# 4_USB.net
KiCad netlist of a schematic drawn in Altium Designer
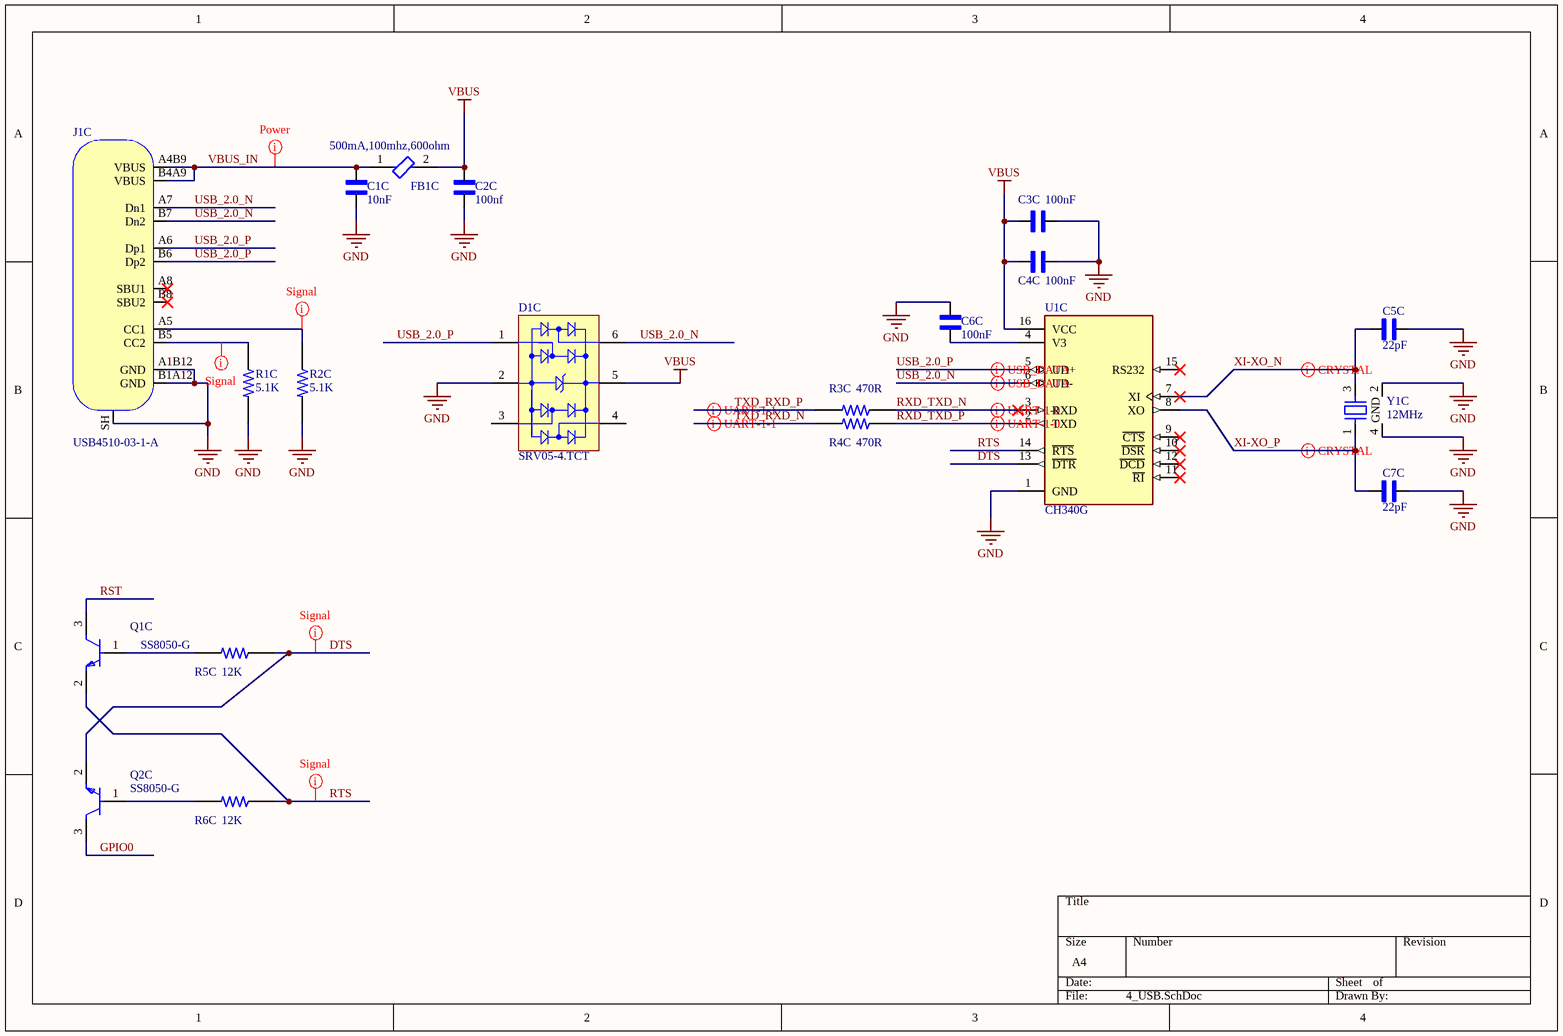
[diagram p0: 4_USB.SchDoc]

(export (version "E")
  (design (tool "Eeschema 10.0.6"))
  (components
    (comp (ref "C1C")
      (value "10nF")
      (footprint "C-0603")
      (description "Ceramic Capacitor 16V 0603 (1608 Metric)")
      (fields (field (name "MP") "C0603C104J4RAC") (field (name "MF") "KEMET"))
      (libsource (lib "ESP01-S-UART") (part "C-0603"))
    )
    (comp (ref "C2C")
      (value "100nf")
      (footprint "C-0603")
      (description "Ceramic Capacitor 16V 0603 (1608 Metric)")
      (fields (field (name "MP") "C0603C104J4RAC") (field (name "MF") "KEMET"))
      (libsource (lib "ESP01-S-UART") (part "C-0603"))
    )
    (comp (ref "C3C")
      (value "100nF")
      (footprint "C-0603")
      (description "Ceramic Capacitor 16V 0603 (1608 Metric)")
      (fields (field (name "MP") "C0603C104J4RAC") (field (name "MF") "KEMET"))
      (libsource (lib "") (part "C-0603_2"))
    )
    (comp (ref "C4C")
      (value "100nF")
      (footprint "C-0603")
      (description "Ceramic Capacitor 16V 0603 (1608 Metric)")
      (fields (field (name "MP") "C0603C104J4RAC") (field (name "MF") "KEMET"))
      (libsource (lib "") (part "C-0603_2"))
    )
    (comp (ref "C5C")
      (value "22pF")
      (footprint "C-0603")
      (description "Ceramic Capacitor 16V 0603 (1608 Metric)")
      (fields (field (name "MP") "C0603C104J4RAC") (field (name "MF") "KEMET"))
      (libsource (lib "") (part "C-0603_1"))
    )
    (comp (ref "C6C")
      (value "100nF")
      (footprint "C-0603")
      (description "Ceramic Capacitor 16V 0603 (1608 Metric)")
      (fields (field (name "MP") "C0603C104J4RAC") (field (name "MF") "KEMET"))
      (libsource (lib "") (part "C-0603_3"))
    )
    (comp (ref "C7C")
      (value "22pF")
      (footprint "C-0603")
      (description "Ceramic Capacitor 16V 0603 (1608 Metric)")
      (fields (field (name "MP") "C0603C104J4RAC") (field (name "MF") "KEMET"))
      (libsource (lib "") (part "C-0603_1"))
    )
    (comp (ref "D1C")
      (value "SRV05-4.TCT")
      (footprint "SMTC-SOT23-6_V")
      (fields (field (name "MANUFACTURER") "Semtech"))
      (libsource (lib "ESP01-S-UART") (part "STM-USB_DVI_HDMIULC6-4SC6X-SOT23-6L"))
    )
    (comp (ref "FB1C")
      (value "500mA,100mhz,600ohm")
      (footprint "FP-BLM21-0_2-t0_85-e0_5-IPC_A")
      (description "BLM21BB121SN1D")
      (fields (field (name "TOLERANCE") "25%"))
      (libsource (lib "ESP01-S-UART") (part "5f30dd21d616792df468990f7003faa"))
    )
    (comp (ref "J1C")
      (value "USB4510-03-1-A")
      (footprint "USB4510-03-1-A")
      (description "USB Connector Type C SMT Mid-Mount 16 Pin")
      (fields (field (name "MANUFACTURER") "GCT"))
      (libsource (lib "ESP01-S-UART") (part "USB4510-03-1-A"))
    )
    (comp (ref "Q1C")
      (value "SS8050-G")
      (footprint "FP-SS8050-G-MFG")
      (description "NPN TRANSISTOR 1.5A 40V SOT-23 R")
      (libsource (lib "ESP01-S-UART") (part "2a1388f82443b098dcd57d24ac7632d"))
    )
    (comp (ref "Q2C")
      (value "SS8050-G")
      (footprint "FP-SS8050-G-MFG")
      (description "NPN TRANSISTOR 1.5A 40V SOT-23 R")
      (libsource (lib "ESP01-S-UART") (part "2a1388f82443b098dcd57d24ac7632d"))
    )
    (comp (ref "R1C")
      (value "5.1K")
      (footprint "R-0603")
      (description "0603")
      (fields (field (name "MP") "2-1623703-0") (field (name "TOLERANCE") "1%"))
      (libsource (lib "ESP01-S-UART") (part "R-0603"))
    )
    (comp (ref "R2C")
      (value "5.1K")
      (footprint "R-0603")
      (description "0603")
      (fields (field (name "MP") "2-1623703-0") (field (name "TOLERANCE") "1%"))
      (libsource (lib "ESP01-S-UART") (part "R-0603"))
    )
    (comp (ref "R3C")
      (value "470R")
      (footprint "R-0603")
      (description "0603")
      (fields (field (name "MP") "2-1623703-0") (field (name "TOLERANCE") "1%"))
      (libsource (lib "ESP01-S-UART") (part "R-0603"))
    )
    (comp (ref "R4C")
      (value "470R")
      (footprint "R-0603")
      (description "0603")
      (fields (field (name "MP") "2-1623703-0") (field (name "TOLERANCE") "1%"))
      (libsource (lib "ESP01-S-UART") (part "R-0603"))
    )
    (comp (ref "R5C")
      (value "12K")
      (footprint "R-0603")
      (description "0603")
      (fields (field (name "MP") "2-1623703-0") (field (name "TOLERANCE") "1%"))
      (libsource (lib "ESP01-S-UART") (part "R-0603"))
    )
    (comp (ref "R6C")
      (value "12K")
      (footprint "R-0603")
      (description "0603")
      (fields (field (name "MP") "2-1623703-0") (field (name "TOLERANCE") "1%"))
      (libsource (lib "ESP01-S-UART") (part "R-0603"))
    )
    (comp (ref "U1C")
      (value "CH340G")
      (footprint "SOIC127P600X180-16N")
      (libsource (lib "ESP01-S-UART") (part "CH340G"))
    )
    (comp (ref "Y1C")
      (value "12MHz")
      (footprint "ABRACON ABM10")
      (description "CRYSTAL 12.00MHZ 8PF LOW ESR SMD")
      (fields
        (field (name "PART NUMBER") "ABM10-167-12.000MHZ-T3")
        (field (name "MANUFACTURER") "Abracon LLC")
      )
      (libsource (lib "ESP01-S-UART") (part "Abracon Crystal ABM10"))
    )
  )
  (nets
    (net (code "1") (name "/DTS") (class "Default")
      (node (ref "Q2C") (pin "2") (pinfunction "E_2") (pintype "passive"))
      (node (ref "R5C") (pin "1") (pinfunction "1_1") (pintype "passive"))
      (node (ref "U1C") (pin "13") (pinfunction "~{DTR}_13") (pintype "output"))
    )
    (net (code "2") (name "/GPIO0") (class "Default")
      (node (ref "Q2C") (pin "3") (pinfunction "C_3") (pintype "passive"))
    )
    (net (code "3") (name "/RST") (class "Default")
      (node (ref "Q1C") (pin "3") (pinfunction "C_3") (pintype "passive"))
    )
    (net (code "4") (name "/RTS") (class "Default")
      (node (ref "Q1C") (pin "2") (pinfunction "E_2") (pintype "passive"))
      (node (ref "R6C") (pin "1") (pinfunction "1_1") (pintype "passive"))
      (node (ref "U1C") (pin "14") (pinfunction "~{RTS}_14") (pintype "output"))
    )
    (net (code "5") (name "/RXD_TXD_N") (class "Default")
      (node (ref "R3C") (pin "1") (pinfunction "1_1") (pintype "passive"))
      (node (ref "U1C") (pin "3") (pinfunction "RXD_3") (pintype "input"))
    )
    (net (code "6") (name "/RXD_TXD_P") (class "Default")
      (node (ref "R4C") (pin "1") (pinfunction "1_1") (pintype "passive"))
      (node (ref "U1C") (pin "2") (pinfunction "TXD_2") (pintype "output"))
    )
    (net (code "7") (name "/TXD_RXD_N") (class "Default")
      (node (ref "R4C") (pin "2") (pinfunction "2_2") (pintype "passive"))
    )
    (net (code "8") (name "/TXD_RXD_P") (class "Default")
      (node (ref "R3C") (pin "2") (pinfunction "2_2") (pintype "passive"))
    )
    (net (code "9") (name "/USB_2.0_N") (class "Default")
      (node (ref "D1C") (pin "6") (pinfunction "I/O_4_6") (pintype "passive"))
      (node (ref "J1C") (pin "A7") (pinfunction "Dn1_A7") (pintype "passive"))
      (node (ref "J1C") (pin "B7") (pinfunction "Dn2_B7") (pintype "passive"))
      (node (ref "U1C") (pin "6") (pinfunction "UD-_6") (pintype "bidirectional"))
    )
    (net (code "10") (name "/USB_2.0_P") (class "Default")
      (node (ref "D1C") (pin "1") (pinfunction "I/O_1_1") (pintype "passive"))
      (node (ref "J1C") (pin "A6") (pinfunction "Dp1_A6") (pintype "passive"))
      (node (ref "J1C") (pin "B6") (pinfunction "Dp2_B6") (pintype "passive"))
      (node (ref "U1C") (pin "5") (pinfunction "UD+_5") (pintype "bidirectional"))
    )
    (net (code "11") (name "/VBUS_IN") (class "Default")
      (node (ref "C1C") (pin "2") (pinfunction "2_2") (pintype "passive"))
      (node (ref "FB1C") (pin "1") (pinfunction "1_1") (pintype "passive"))
      (node (ref "J1C") (pin "A4B9") (pinfunction "VBUS_A4B9") (pintype "passive"))
      (node (ref "J1C") (pin "B4A9") (pinfunction "VBUS_B4A9") (pintype "passive"))
    )
    (net (code "12") (name "/XI-XO_N") (class "Default")
      (node (ref "C5C") (pin "1") (pinfunction "1_1") (pintype "passive"))
      (node (ref "U1C") (pin "7") (pinfunction "XI_7") (pintype "input"))
      (node (ref "Y1C") (pin "3") (pinfunction "3_3") (pintype "passive"))
    )
    (net (code "13") (name "/XI-XO_P") (class "Default")
      (node (ref "C7C") (pin "1") (pinfunction "1_1") (pintype "passive"))
      (node (ref "U1C") (pin "8") (pinfunction "XO_8") (pintype "output"))
      (node (ref "Y1C") (pin "1") (pinfunction "1_1") (pintype "passive"))
    )
    (net (code "14") (name "GND") (class "Default")
      (node (ref "C1C") (pin "1") (pinfunction "1_1") (pintype "passive"))
      (node (ref "C2C") (pin "1") (pinfunction "1_1") (pintype "passive"))
      (node (ref "C3C") (pin "1") (pinfunction "1_1") (pintype "passive"))
      (node (ref "C4C") (pin "1") (pinfunction "1_1") (pintype "passive"))
      (node (ref "C5C") (pin "2") (pinfunction "2_2") (pintype "passive"))
      (node (ref "C6C") (pin "1") (pinfunction "1_1") (pintype "passive"))
      (node (ref "C7C") (pin "2") (pinfunction "2_2") (pintype "passive"))
      (node (ref "D1C") (pin "2") (pinfunction "GND_2") (pintype "passive"))
      (node (ref "J1C") (pin "A1B12") (pinfunction "GND_A1B12") (pintype "passive"))
      (node (ref "J1C") (pin "B1A12") (pinfunction "GND_B1A12") (pintype "passive"))
      (node (ref "J1C") (pin "SH") (pinfunction "SHIELD_SH") (pintype "passive"))
      (node (ref "R1C") (pin "2") (pinfunction "2_2") (pintype "passive"))
      (node (ref "R2C") (pin "2") (pinfunction "2_2") (pintype "passive"))
      (node (ref "U1C") (pin "1") (pinfunction "GND_1") (pintype "power_in"))
      (node (ref "Y1C") (pin "2") (pinfunction "GND_2") (pintype "passive"))
      (node (ref "Y1C") (pin "4") (pinfunction "GND_4") (pintype "passive"))
    )
    (net (code "15") (name "Net-(J1C-CC1)") (class "Default")
      (node (ref "J1C") (pin "A5") (pinfunction "CC1_A5") (pintype "passive"))
      (node (ref "R2C") (pin "1") (pinfunction "1_1") (pintype "passive"))
    )
    (net (code "16") (name "Net-(J1C-CC2)") (class "Default")
      (node (ref "J1C") (pin "B5") (pinfunction "CC2_B5") (pintype "passive"))
      (node (ref "R1C") (pin "1") (pinfunction "1_1") (pintype "passive"))
    )
    (net (code "17") (name "Net-(Q1C-B)") (class "Default")
      (node (ref "Q1C") (pin "1") (pinfunction "B_1") (pintype "passive"))
      (node (ref "R5C") (pin "2") (pinfunction "2_2") (pintype "passive"))
    )
    (net (code "18") (name "Net-(Q2C-B)") (class "Default")
      (node (ref "Q2C") (pin "1") (pinfunction "B_1") (pintype "passive"))
      (node (ref "R6C") (pin "2") (pinfunction "2_2") (pintype "passive"))
    )
    (net (code "19") (name "Net-(U1C-V3)") (class "Default")
      (node (ref "C6C") (pin "2") (pinfunction "2_2") (pintype "passive"))
      (node (ref "U1C") (pin "4") (pinfunction "V3_4") (pintype "power_in"))
    )
    (net (code "20") (name "VBUS") (class "Default")
      (node (ref "C2C") (pin "2") (pinfunction "2_2") (pintype "passive"))
      (node (ref "C3C") (pin "2") (pinfunction "2_2") (pintype "passive"))
      (node (ref "C4C") (pin "2") (pinfunction "2_2") (pintype "passive"))
      (node (ref "D1C") (pin "5") (pinfunction "VBUS_5") (pintype "passive"))
      (node (ref "FB1C") (pin "2") (pinfunction "2_2") (pintype "passive"))
      (node (ref "U1C") (pin "16") (pinfunction "VCC_16") (pintype "power_in"))
    )
    (net (code "21") (name "unconnected-(D1C-I{slash}O_2-Pad3)") (class "Default")
      (node (ref "D1C") (pin "3") (pinfunction "I/O_2_3") (pintype "passive"))
    )
    (net (code "22") (name "unconnected-(D1C-I{slash}O_3-Pad4)") (class "Default")
      (node (ref "D1C") (pin "4") (pinfunction "I/O_3_4") (pintype "passive"))
    )
    (net (code "23") (name "unconnected-(J1C-SBU1-PadA8)") (class "Default")
      (node (ref "J1C") (pin "A8") (pinfunction "SBU1_A8") (pintype "passive+no_connect"))
    )
    (net (code "24") (name "unconnected-(J1C-SBU2-PadB8)") (class "Default")
      (node (ref "J1C") (pin "B8") (pinfunction "SBU2_B8") (pintype "passive+no_connect"))
    )
    (net (code "25") (name "unconnected-(U1C-RS232-Pad15)") (class "Default")
      (node (ref "U1C") (pin "15") (pinfunction "RS232_15") (pintype "input+no_connect"))
    )
    (net (code "26") (name "unconnected-(U1C-~{CTS}-Pad9)") (class "Default")
      (node (ref "U1C") (pin "9") (pinfunction "~{CTS}_9") (pintype "input+no_connect"))
    )
    (net (code "27") (name "unconnected-(U1C-~{DCD}-Pad12)") (class "Default")
      (node (ref "U1C") (pin "12") (pinfunction "~{DCD}_12") (pintype "input+no_connect"))
    )
    (net (code "28") (name "unconnected-(U1C-~{DSR}-Pad10)") (class "Default")
      (node (ref "U1C") (pin "10") (pinfunction "~{DSR}_10") (pintype "input+no_connect"))
    )
    (net (code "29") (name "unconnected-(U1C-~{RI}-Pad11)") (class "Default")
      (node (ref "U1C") (pin "11") (pinfunction "~{RI}_11") (pintype "input+no_connect"))
    )
  )
)
